# SCH_Hack-Card_2025-07-14.net
KiCad netlist of a schematic drawn in EasyEDA
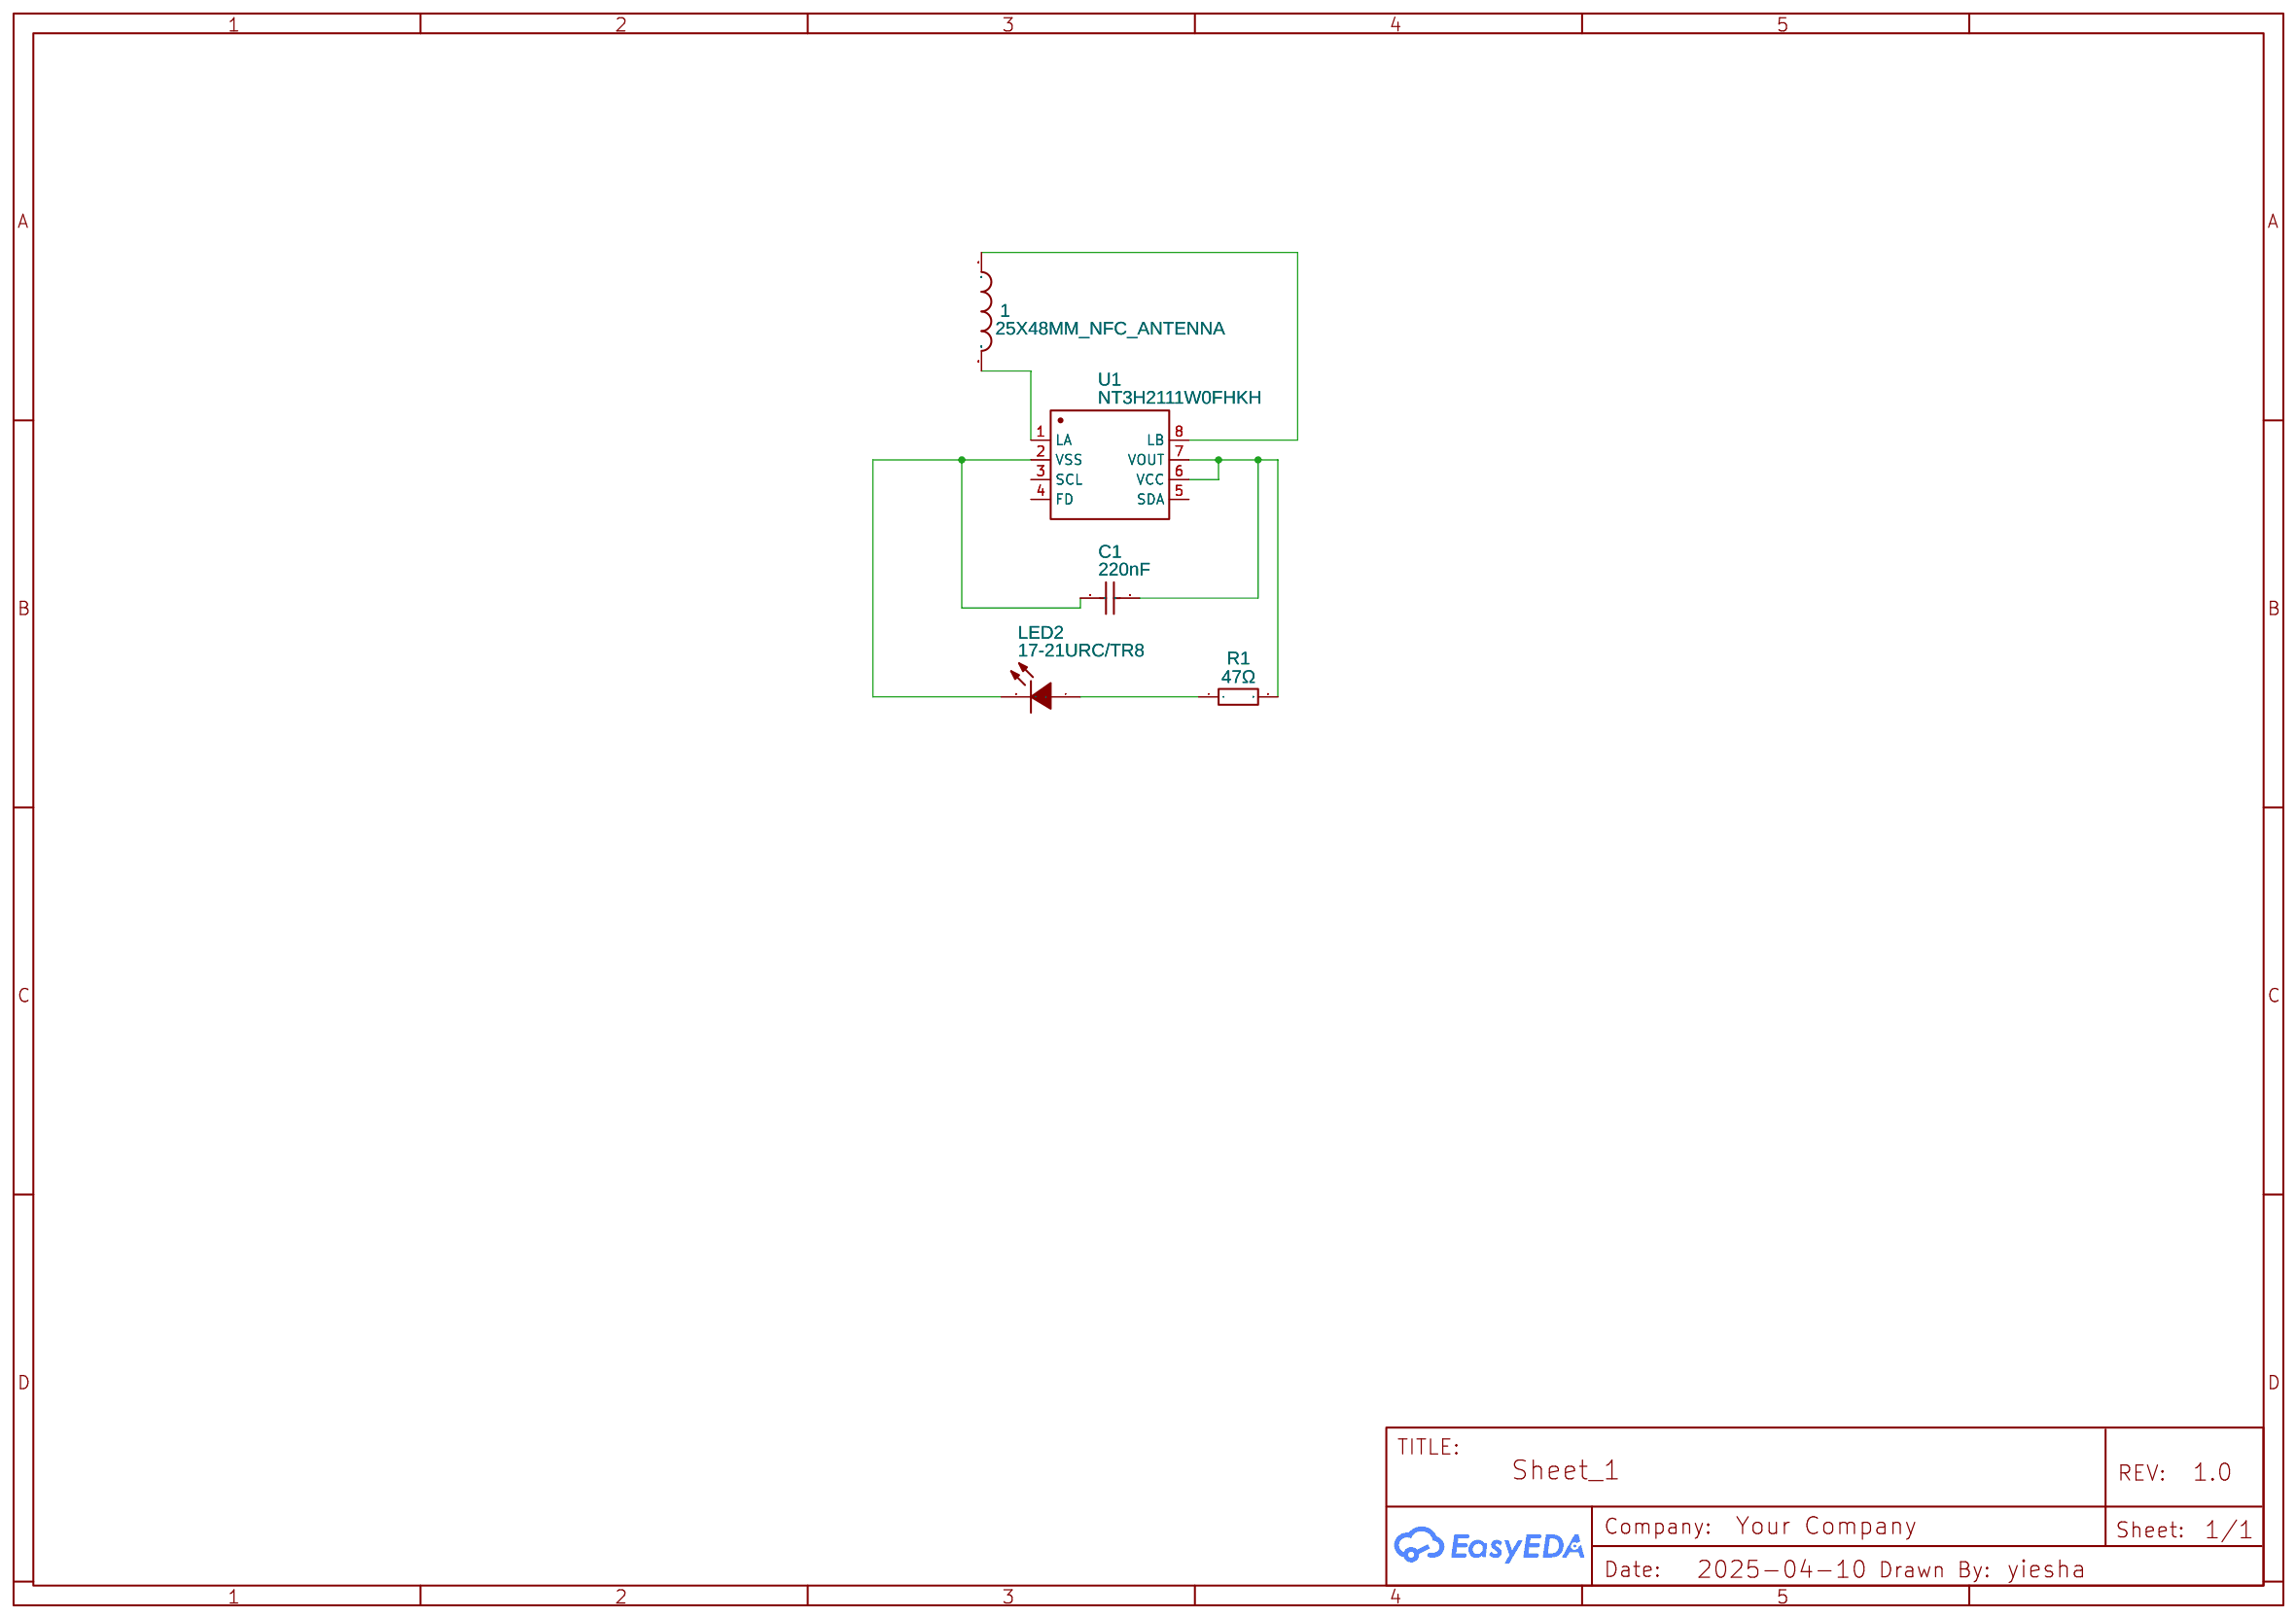
[diagram p0: schematic sheet]

(export (version "E")
  (design (tool "Eeschema 10.0.6"))
  (components
    (comp (ref "1") (value "25X48MM_NFC_ANTENNA") (libsource (lib "") (part "25X48MM_NFC_ANTENNA")))
    (comp (ref "C1")
      (value "220nF")
      (fields
        (field (name "Manufacturer Part") "CL10B224KA8NNNC")
        (field (name "Manufacturer") "SAMSUNG(三星)")
      )
      (libsource (lib "") (part "CL10B224KA8NNNC"))
    )
    (comp (ref "LED2")
      (value "17-21URC/TR8")
      (fields (field (name "Manufacturer") "EVERLIGHT(亿光)"))
      (libsource (lib "") (part "17-21URC/TR8"))
    )
    (comp (ref "R1")
      (value "47Ω")
      (fields
        (field (name "Manufacturer Part") "0603WAF470JT5E")
        (field (name "Manufacturer") "UNI-ROYAL(厚声)")
      )
      (libsource (lib "") (part "0603WAF470JT5E"))
    )
    (comp (ref "U1")
      (value "NT3H2111W0FHKH")
      (fields (field (name "Manufacturer") "NXP(恩智浦)"))
      (libsource (lib "") (part "NT3H2111W0FHKH"))
    )
  )
  (nets
    (net (code "1") (name "Net-(LED2-A)") (class "Default")
      (node (ref "LED2") (pin "1") (pinfunction "A_1") (pintype "unspecified"))
      (node (ref "R1") (pin "1") (pinfunction "1_1") (pintype "input"))
    )
    (net (code "2") (name "Net-(LED2-K)") (class "Default")
      (node (ref "C1") (pin "1") (pinfunction "1_1") (pintype "input"))
      (node (ref "LED2") (pin "2") (pinfunction "K_2") (pintype "unspecified"))
      (node (ref "U1") (pin "2") (pinfunction "VSS_2") (pintype "unspecified"))
    )
    (net (code "3") (name "Net-(U1-LA)") (class "Default")
      (node (ref "1") (pin "P$2") (pinfunction "P$2_P$2") (pintype "bidirectional"))
      (node (ref "U1") (pin "1") (pinfunction "LA_1") (pintype "unspecified"))
    )
    (net (code "4") (name "Net-(U1-LB)") (class "Default")
      (node (ref "1") (pin "P$1") (pinfunction "P$1_P$1") (pintype "bidirectional"))
      (node (ref "U1") (pin "8") (pinfunction "LB_8") (pintype "unspecified"))
    )
    (net (code "5") (name "Net-(U1-VCC)") (class "Default")
      (node (ref "C1") (pin "2") (pinfunction "2_2") (pintype "input"))
      (node (ref "R1") (pin "2") (pinfunction "2_2") (pintype "input"))
      (node (ref "U1") (pin "6") (pinfunction "VCC_6") (pintype "unspecified"))
      (node (ref "U1") (pin "7") (pinfunction "VOUT_7") (pintype "unspecified"))
    )
    (net (code "6") (name "unconnected-(U1-FD-Pad4)") (class "Default")
      (node (ref "U1") (pin "4") (pinfunction "FD_4") (pintype "unspecified"))
    )
    (net (code "7") (name "unconnected-(U1-SCL-Pad3)") (class "Default")
      (node (ref "U1") (pin "3") (pinfunction "SCL_3") (pintype "unspecified"))
    )
    (net (code "8") (name "unconnected-(U1-SDA-Pad5)") (class "Default")
      (node (ref "U1") (pin "5") (pinfunction "SDA_5") (pintype "unspecified"))
    )
  )
)
